# RescueLS.net
KiCad netlist of a schematic drawn in EAGLE
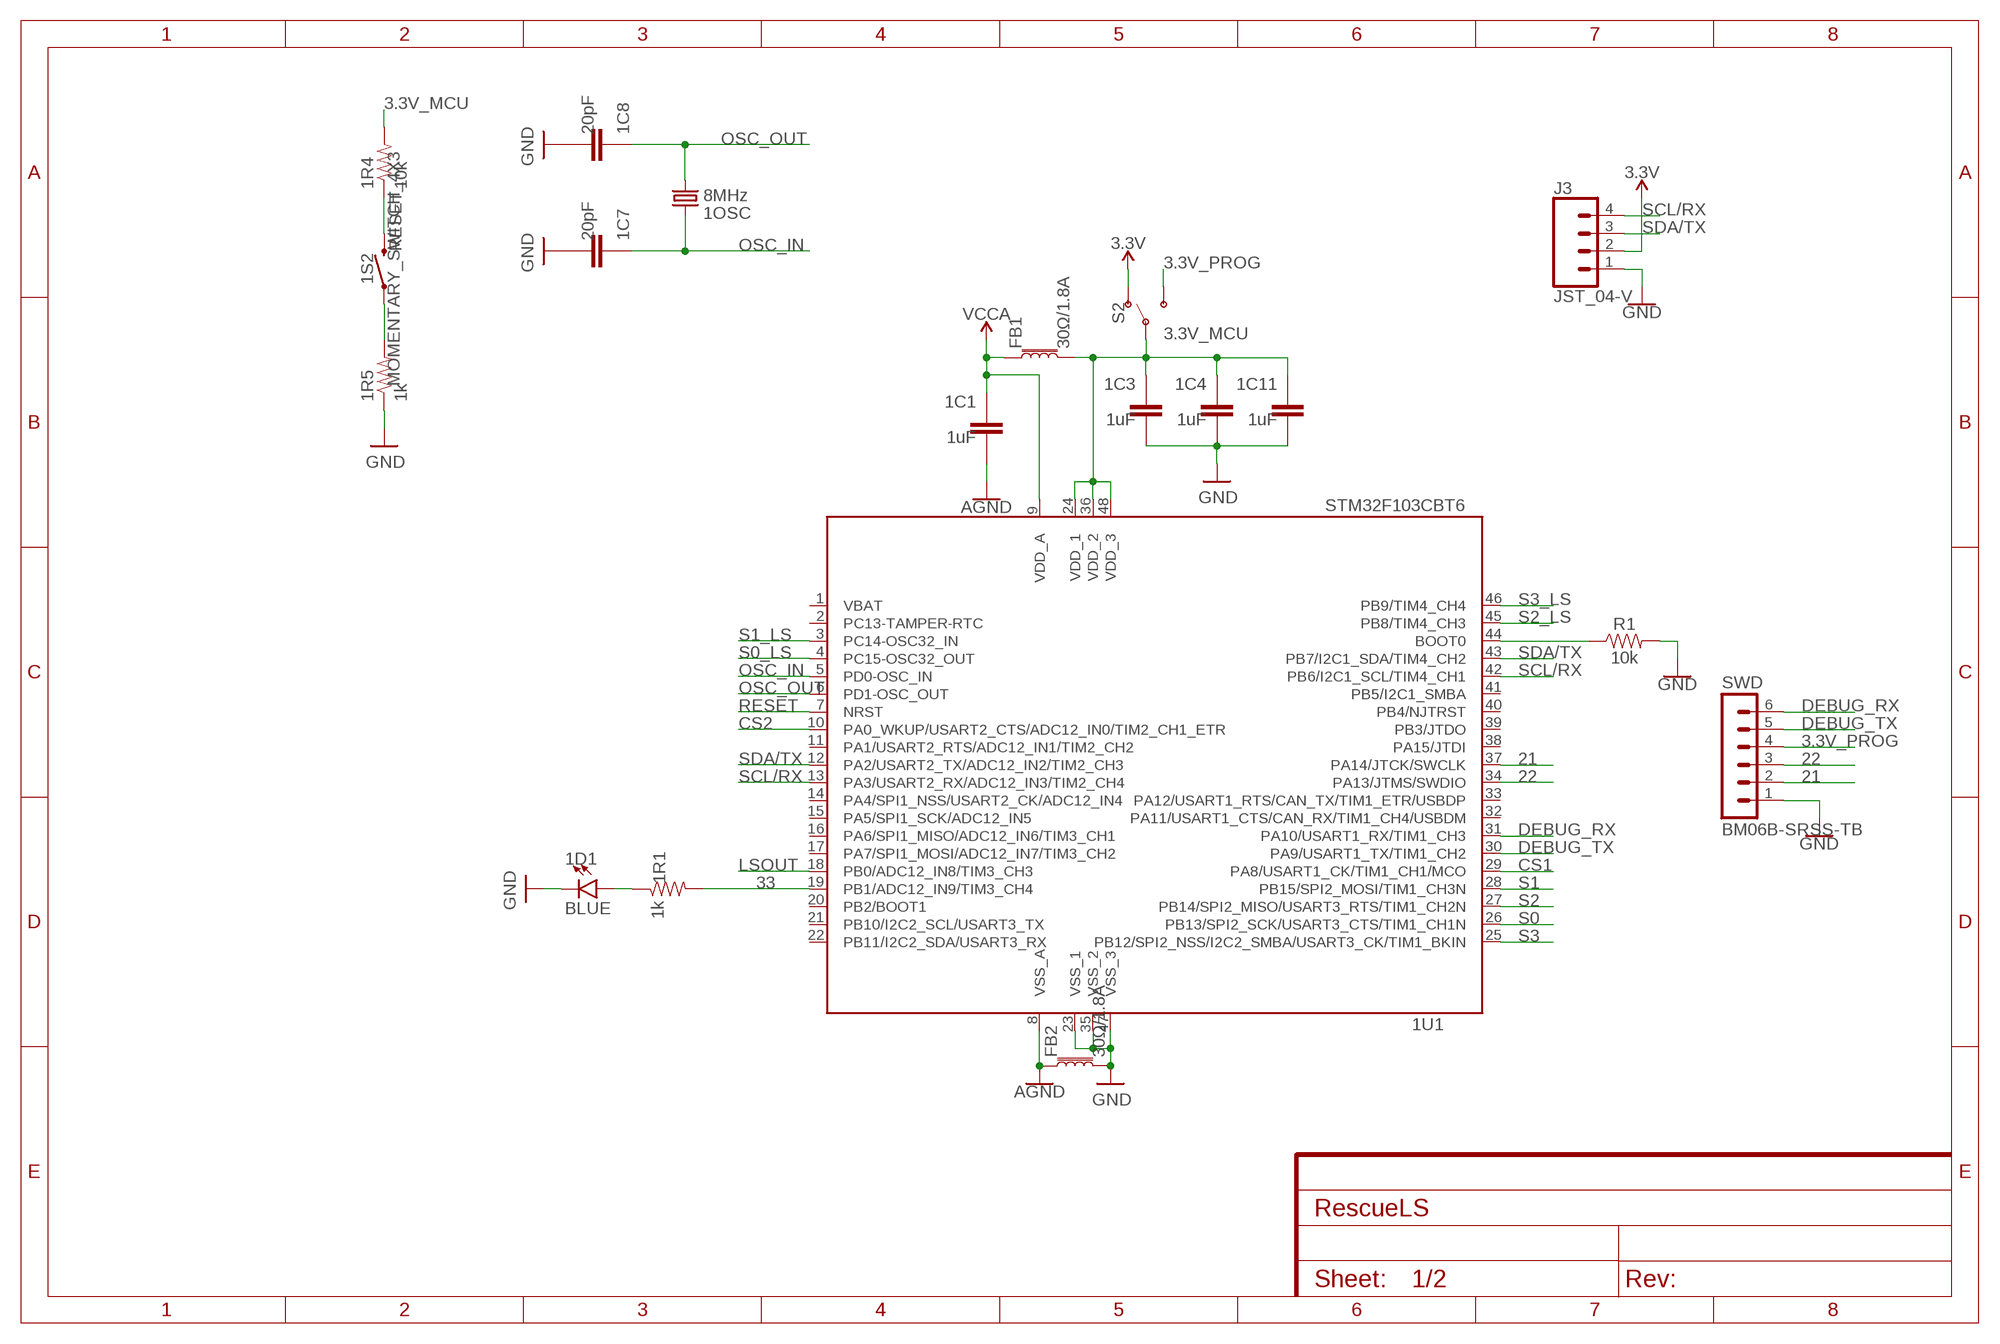
[diagram p0: schematic, sheet 1]
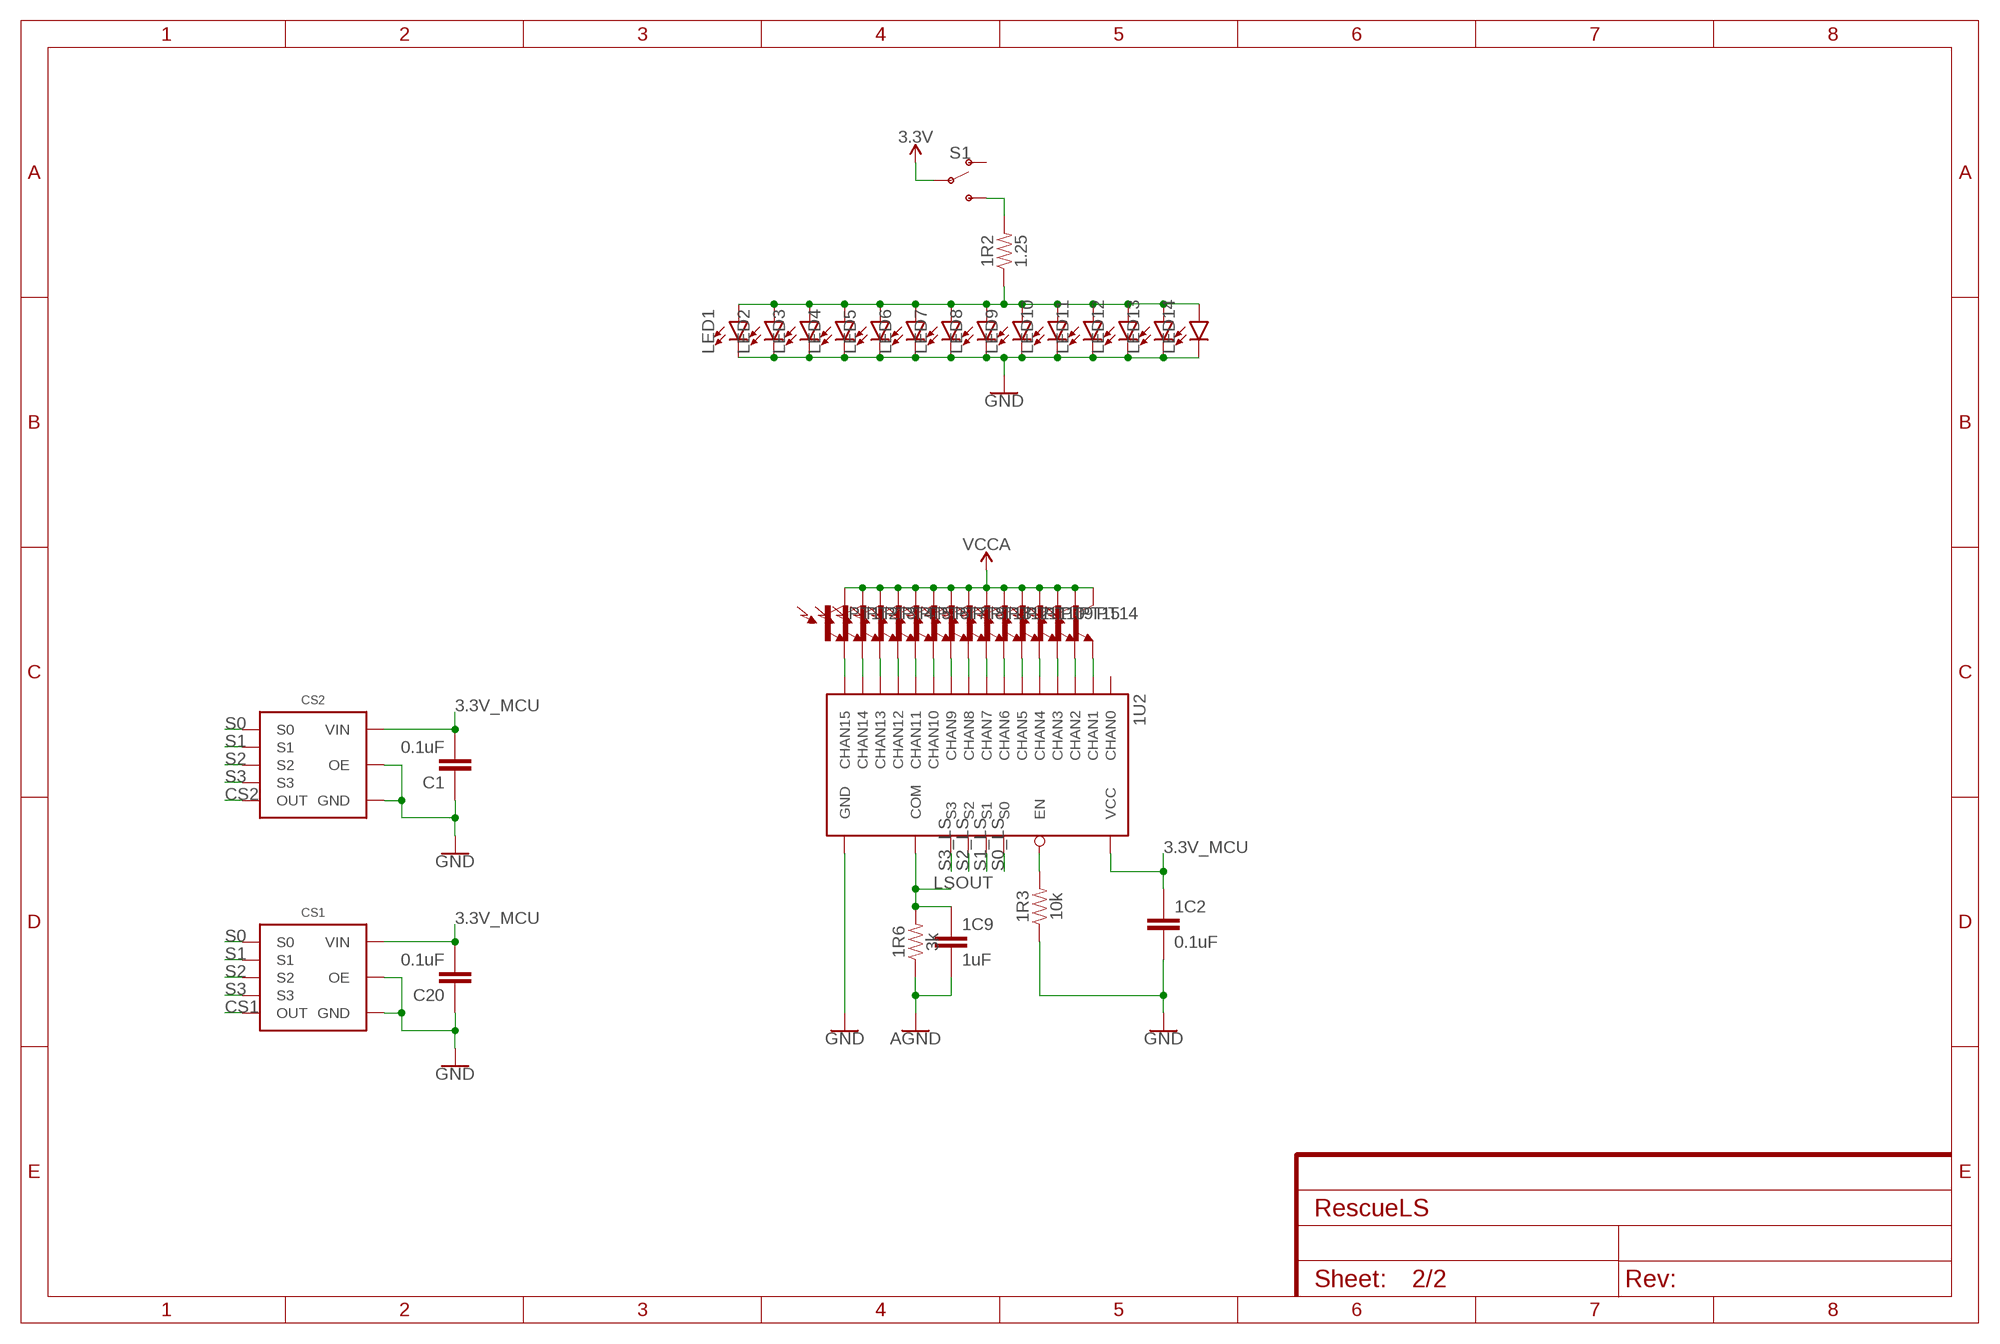
[diagram p1: schematic, sheet 2]

(export (version "E")
  (design (tool "Eeschema 10.0.6"))
  (components
    (comp (ref "1C1")
      (value "1uF")
      (footprint "eagle-import:C0603")
      (libsource (lib "eagle-import") (part "CAPACITOR0603"))
    )
    (comp (ref "1C3")
      (value "1uF")
      (footprint "eagle-import:C0603")
      (libsource (lib "eagle-import") (part "CAPACITOR0603"))
    )
    (comp (ref "1C4")
      (value "1uF")
      (footprint "eagle-import:C0603")
      (libsource (lib "eagle-import") (part "CAPACITOR0603"))
    )
    (comp (ref "1C7")
      (value "20pF")
      (footprint "eagle-import:C0603")
      (libsource (lib "eagle-import") (part "CAPACITOR0603"))
    )
    (comp (ref "1C8")
      (value "20pF")
      (footprint "eagle-import:C0603")
      (libsource (lib "eagle-import") (part "CAPACITOR0603"))
    )
    (comp (ref "1C11")
      (value "1uF")
      (footprint "eagle-import:C0603")
      (libsource (lib "eagle-import") (part "CAPACITOR0603"))
    )
    (comp (ref "1D1")
      (value "BLUE")
      (footprint "eagle-import:LED-0603")
      (libsource (lib "eagle-import") (part "LED-BLUE0603"))
    )
    (comp (ref "1OSC")
      (value "8MHz")
      (footprint "eagle-import:CRYSTAL-SMD-5X3.2-2PAD")
      (libsource (lib "eagle-import") (part "CRYSTALSMD-5X3.2-2PAD"))
    )
    (comp (ref "1R1")
      (value "1k")
      (footprint "eagle-import:R0603")
      (libsource (lib "eagle-import") (part "RESISTOR0603"))
    )
    (comp (ref "1R4")
      (value "10k")
      (footprint "eagle-import:R0603")
      (libsource (lib "eagle-import") (part "RESISTOR0603"))
    )
    (comp (ref "1R5")
      (value "1k")
      (footprint "eagle-import:R0603")
      (libsource (lib "eagle-import") (part "RESISTOR0603"))
    )
    (comp (ref "1S2")
      (value "MOMENTARY_SWITCH_4X3")
      (footprint "eagle-import:MOMENTARY_SWITCH_4X3")
      (libsource (lib "eagle-import") (part "MOMENTARY_SWITCH_4X3"))
    )
    (comp (ref "1U1")
      (value "STM32F103CBT6")
      (footprint "eagle-import:LQFP48")
      (libsource (lib "eagle-import") (part "STM32F103CBT6"))
    )
    (comp (ref "FB1")
      (value "30Ω/1.8A")
      (footprint "eagle-import:0603")
      (libsource (lib "eagle-import") (part "FERRITE_BEAD-0603"))
    )
    (comp (ref "FB2")
      (value "30Ω/1.8A")
      (footprint "eagle-import:0603")
      (libsource (lib "eagle-import") (part "FERRITE_BEAD-0603"))
    )
    (comp (ref "J3")
      (value "JST_04-V")
      (footprint "eagle-import:JST_04-V")
      (libsource (lib "eagle-import") (part "JST_04-V"))
    )
    (comp (ref "R1")
      (value "10k")
      (footprint "eagle-import:R0603")
      (libsource (lib "eagle-import") (part "RESISTOR0603"))
    )
    (comp (ref "S2")
      (value "SWITCH-SPDT-PTH-11.6X4.0MM-LOCK")
      (footprint "eagle-import:SWITCH_SPDT_PTH_11.6X4.0MM_LOCK")
      (libsource (lib "eagle-import") (part "SWITCH-SPDT-PTH-11.6X4.0MM-LOCK"))
    )
    (comp (ref "SWD")
      (value "BM06B-SRSS-TB")
      (footprint "eagle-import:BM06B-SRSS-TB")
      (libsource (lib "eagle-import") (part "BM06B-SRSS-TB"))
    )
    (comp (ref "1C2")
      (value "0.1uF")
      (footprint "eagle-import:C0603")
      (libsource (lib "eagle-import") (part "CAPACITOR0603"))
    )
    (comp (ref "1C9")
      (value "1uF")
      (footprint "eagle-import:C0603")
      (libsource (lib "eagle-import") (part "CAPACITOR0603"))
    )
    (comp (ref "1R2")
      (value "1.25")
      (footprint "eagle-import:R0603")
      (libsource (lib "eagle-import") (part "RESISTOR0603"))
    )
    (comp (ref "1R3")
      (value "10k")
      (footprint "eagle-import:R0603")
      (libsource (lib "eagle-import") (part "RESISTOR0603"))
    )
    (comp (ref "1R6")
      (value "3k")
      (footprint "eagle-import:R0603")
      (libsource (lib "eagle-import") (part "RESISTOR0603"))
    )
    (comp (ref "1U2")
      (value "74HC4067")
      (footprint "eagle-import:SOIC-24")
      (libsource (lib "eagle-import") (part "74HC4067"))
    )
    (comp (ref "C1")
      (value "0.1uF")
      (footprint "eagle-import:C0603")
      (libsource (lib "eagle-import") (part "CAPACITOR0603"))
    )
    (comp (ref "C20")
      (value "0.1uF")
      (footprint "eagle-import:C0603")
      (libsource (lib "eagle-import") (part "CAPACITOR0603"))
    )
    (comp (ref "CS1")
      (value "TCS3200")
      (footprint "eagle-import:SOIC-8")
      (libsource (lib "eagle-import") (part "TCS3200"))
    )
    (comp (ref "CS2")
      (value "TCS3200")
      (footprint "eagle-import:SOIC-8")
      (libsource (lib "eagle-import") (part "TCS3200"))
    )
    (comp (ref "LED1")
      (value "3528LED")
      (footprint "eagle-import:3528")
      (libsource (lib "eagle-import") (part "3528LED"))
    )
    (comp (ref "LED2")
      (value "3528LED")
      (footprint "eagle-import:3528")
      (libsource (lib "eagle-import") (part "3528LED"))
    )
    (comp (ref "LED3")
      (value "3528LED")
      (footprint "eagle-import:3528")
      (libsource (lib "eagle-import") (part "3528LED"))
    )
    (comp (ref "LED4")
      (value "3528LED")
      (footprint "eagle-import:3528")
      (libsource (lib "eagle-import") (part "3528LED"))
    )
    (comp (ref "LED5")
      (value "3528LED")
      (footprint "eagle-import:3528")
      (libsource (lib "eagle-import") (part "3528LED"))
    )
    (comp (ref "LED6")
      (value "3528LED")
      (footprint "eagle-import:3528")
      (libsource (lib "eagle-import") (part "3528LED"))
    )
    (comp (ref "LED7")
      (value "3528LED")
      (footprint "eagle-import:3528")
      (libsource (lib "eagle-import") (part "3528LED"))
    )
    (comp (ref "LED8")
      (value "3528LED")
      (footprint "eagle-import:3528")
      (libsource (lib "eagle-import") (part "3528LED"))
    )
    (comp (ref "LED9")
      (value "3528LED")
      (footprint "eagle-import:3528")
      (libsource (lib "eagle-import") (part "3528LED"))
    )
    (comp (ref "LED10")
      (value "3528LED")
      (footprint "eagle-import:3528")
      (libsource (lib "eagle-import") (part "3528LED"))
    )
    (comp (ref "LED11")
      (value "3528LED")
      (footprint "eagle-import:3528")
      (libsource (lib "eagle-import") (part "3528LED"))
    )
    (comp (ref "LED12")
      (value "3528LED")
      (footprint "eagle-import:3528")
      (libsource (lib "eagle-import") (part "3528LED"))
    )
    (comp (ref "LED13")
      (value "3528LED")
      (footprint "eagle-import:3528")
      (libsource (lib "eagle-import") (part "3528LED"))
    )
    (comp (ref "LED14")
      (value "3528LED")
      (footprint "eagle-import:3528")
      (libsource (lib "eagle-import") (part "3528LED"))
    )
    (comp (ref "PT1")
      (value "LIGHT_SENSORALS")
      (footprint "eagle-import:ALS-PT19")
      (libsource (lib "eagle-import") (part "LIGHT_SENSORALS"))
    )
    (comp (ref "PT2")
      (value "LIGHT_SENSORALS")
      (footprint "eagle-import:ALS-PT19")
      (libsource (lib "eagle-import") (part "LIGHT_SENSORALS"))
    )
    (comp (ref "PT3")
      (value "LIGHT_SENSORALS")
      (footprint "eagle-import:ALS-PT19")
      (libsource (lib "eagle-import") (part "LIGHT_SENSORALS"))
    )
    (comp (ref "PT4")
      (value "LIGHT_SENSORALS")
      (footprint "eagle-import:ALS-PT19")
      (libsource (lib "eagle-import") (part "LIGHT_SENSORALS"))
    )
    (comp (ref "PT5")
      (value "LIGHT_SENSORALS")
      (footprint "eagle-import:ALS-PT19")
      (libsource (lib "eagle-import") (part "LIGHT_SENSORALS"))
    )
    (comp (ref "PT6")
      (value "LIGHT_SENSORALS")
      (footprint "eagle-import:ALS-PT19")
      (libsource (lib "eagle-import") (part "LIGHT_SENSORALS"))
    )
    (comp (ref "PT7")
      (value "LIGHT_SENSORALS")
      (footprint "eagle-import:ALS-PT19")
      (libsource (lib "eagle-import") (part "LIGHT_SENSORALS"))
    )
    (comp (ref "PT8")
      (value "LIGHT_SENSORALS")
      (footprint "eagle-import:ALS-PT19")
      (libsource (lib "eagle-import") (part "LIGHT_SENSORALS"))
    )
    (comp (ref "PT9")
      (value "LIGHT_SENSORALS")
      (footprint "eagle-import:ALS-PT19")
      (libsource (lib "eagle-import") (part "LIGHT_SENSORALS"))
    )
    (comp (ref "PT10")
      (value "LIGHT_SENSORALS")
      (footprint "eagle-import:ALS-PT19")
      (libsource (lib "eagle-import") (part "LIGHT_SENSORALS"))
    )
    (comp (ref "PT11")
      (value "LIGHT_SENSORALS")
      (footprint "eagle-import:ALS-PT19")
      (libsource (lib "eagle-import") (part "LIGHT_SENSORALS"))
    )
    (comp (ref "PT12")
      (value "LIGHT_SENSORALS")
      (footprint "eagle-import:ALS-PT19")
      (libsource (lib "eagle-import") (part "LIGHT_SENSORALS"))
    )
    (comp (ref "PT13")
      (value "LIGHT_SENSORALS")
      (footprint "eagle-import:ALS-PT19")
      (libsource (lib "eagle-import") (part "LIGHT_SENSORALS"))
    )
    (comp (ref "PT14")
      (value "LIGHT_SENSORALS")
      (footprint "eagle-import:ALS-PT19")
      (libsource (lib "eagle-import") (part "LIGHT_SENSORALS"))
    )
    (comp (ref "PT15")
      (value "LIGHT_SENSORALS")
      (footprint "eagle-import:ALS-PT19")
      (libsource (lib "eagle-import") (part "LIGHT_SENSORALS"))
    )
    (comp (ref "S1")
      (value "SWITCH-SPDT-PTH-11.6X4.0MM-LOCK")
      (footprint "eagle-import:SWITCH_SPDT_PTH_11.6X4.0MM_LOCK")
      (libsource (lib "eagle-import") (part "SWITCH-SPDT-PTH-11.6X4.0MM-LOCK"))
    )
  )
  (nets
    (net (code "1") (name "3.3V") (class "Default")
      (node (ref "J3") (pin "2") (pinfunction "2_2") (pintype "passive"))
      (node (ref "S1") (pin "2") (pinfunction "P_2") (pintype "passive"))
      (node (ref "S2") (pin "1") (pinfunction "O_1") (pintype "passive"))
    )
    (net (code "2") (name "3.3V_MCU") (class "Default")
      (node (ref "1C11") (pin "1") (pinfunction "1_1") (pintype "passive"))
      (node (ref "1C2") (pin "1") (pinfunction "1_1") (pintype "passive"))
      (node (ref "1C3") (pin "1") (pinfunction "1_1") (pintype "passive"))
      (node (ref "1C4") (pin "1") (pinfunction "1_1") (pintype "passive"))
      (node (ref "1R4") (pin "2") (pinfunction "2_2") (pintype "passive"))
      (node (ref "1U1") (pin "24") (pinfunction "VDD_1_24") (pintype "power_in"))
      (node (ref "1U1") (pin "36") (pinfunction "VDD_2_36") (pintype "power_in"))
      (node (ref "1U1") (pin "48") (pinfunction "VDD_3_48") (pintype "power_in"))
      (node (ref "1U2") (pin "P24") (pinfunction "VCC_P24") (pintype "bidirectional"))
      (node (ref "C1") (pin "2") (pinfunction "2_2") (pintype "passive"))
      (node (ref "C20") (pin "2") (pinfunction "2_2") (pintype "passive"))
      (node (ref "CS1") (pin "5") (pinfunction "VIN_5") (pintype "bidirectional"))
      (node (ref "CS2") (pin "5") (pinfunction "VIN_5") (pintype "bidirectional"))
      (node (ref "FB1") (pin "2") (pinfunction "2_2") (pintype "passive"))
      (node (ref "S2") (pin "2") (pinfunction "P_2") (pintype "passive"))
    )
    (net (code "3") (name "3.3V_PROG") (class "Default")
      (node (ref "S2") (pin "3") (pinfunction "S_3") (pintype "passive"))
      (node (ref "SWD") (pin "4") (pinfunction "4_4") (pintype "passive"))
    )
    (net (code "4") (name "21") (class "Default")
      (node (ref "1U1") (pin "37") (pinfunction "PA14/JTCK/SWCLK_37") (pintype "bidirectional"))
      (node (ref "SWD") (pin "2") (pinfunction "2_2") (pintype "passive"))
    )
    (net (code "5") (name "22") (class "Default")
      (node (ref "1U1") (pin "34") (pinfunction "PA13/JTMS/SWDIO_34") (pintype "bidirectional"))
      (node (ref "SWD") (pin "3") (pinfunction "3_3") (pintype "passive"))
    )
    (net (code "6") (name "33") (class "Default")
      (node (ref "1R1") (pin "2") (pinfunction "2_2") (pintype "passive"))
      (node (ref "1U1") (pin "19") (pinfunction "PB1/ADC12_IN9/TIM3_CH4_19") (pintype "bidirectional"))
    )
    (net (code "7") (name "AGND") (class "Default")
      (node (ref "1C1") (pin "2") (pinfunction "2_2") (pintype "passive"))
      (node (ref "1C9") (pin "2") (pinfunction "2_2") (pintype "passive"))
      (node (ref "1R6") (pin "1") (pinfunction "1_1") (pintype "passive"))
      (node (ref "1U1") (pin "8") (pinfunction "VSS_A_8") (pintype "power_in"))
      (node (ref "FB2") (pin "1") (pinfunction "1_1") (pintype "passive"))
    )
    (net (code "8") (name "CS1") (class "Default")
      (node (ref "1U1") (pin "29") (pinfunction "PA8/USART1_CK/TIM1_CH1/MCO_29") (pintype "bidirectional"))
      (node (ref "CS1") (pin "6") (pinfunction "OUT_6") (pintype "bidirectional"))
    )
    (net (code "9") (name "CS2") (class "Default")
      (node (ref "1U1") (pin "10") (pinfunction "PA0_WKUP/USART2_CTS/ADC12_IN0/TIM2_CH1_ETR_10") (pintype "bidirectional"))
      (node (ref "CS2") (pin "6") (pinfunction "OUT_6") (pintype "bidirectional"))
    )
    (net (code "10") (name "DEBUG_RX") (class "Default")
      (node (ref "1U1") (pin "31") (pinfunction "PA10/USART1_RX/TIM1_CH3_31") (pintype "bidirectional"))
      (node (ref "SWD") (pin "6") (pinfunction "6_6") (pintype "passive"))
    )
    (net (code "11") (name "DEBUG_TX") (class "Default")
      (node (ref "1U1") (pin "30") (pinfunction "PA9/USART1_TX/TIM1_CH2_30") (pintype "input"))
      (node (ref "SWD") (pin "5") (pinfunction "5_5") (pintype "passive"))
    )
    (net (code "12") (name "GND") (class "Default")
      (node (ref "1C11") (pin "2") (pinfunction "2_2") (pintype "passive"))
      (node (ref "1C2") (pin "2") (pinfunction "2_2") (pintype "passive"))
      (node (ref "1C3") (pin "2") (pinfunction "2_2") (pintype "passive"))
      (node (ref "1C4") (pin "2") (pinfunction "2_2") (pintype "passive"))
      (node (ref "1C7") (pin "2") (pinfunction "2_2") (pintype "passive"))
      (node (ref "1C8") (pin "2") (pinfunction "2_2") (pintype "passive"))
      (node (ref "1D1") (pin "C") (pinfunction "C_C") (pintype "passive"))
      (node (ref "1R3") (pin "1") (pinfunction "1_1") (pintype "passive"))
      (node (ref "1R5") (pin "1") (pinfunction "1_1") (pintype "passive"))
      (node (ref "1U1") (pin "23") (pinfunction "VSS_1_23") (pintype "power_in"))
      (node (ref "1U1") (pin "35") (pinfunction "VSS_2_35") (pintype "power_in"))
      (node (ref "1U1") (pin "47") (pinfunction "VSS_3_47") (pintype "power_in"))
      (node (ref "1U2") (pin "P12") (pinfunction "GND_P12") (pintype "bidirectional"))
      (node (ref "C1") (pin "1") (pinfunction "1_1") (pintype "passive"))
      (node (ref "C20") (pin "1") (pinfunction "1_1") (pintype "passive"))
      (node (ref "CS1") (pin "3") (pinfunction "OE_3") (pintype "bidirectional"))
      (node (ref "CS1") (pin "4") (pinfunction "GND_4") (pintype "bidirectional"))
      (node (ref "CS2") (pin "3") (pinfunction "OE_3") (pintype "bidirectional"))
      (node (ref "CS2") (pin "4") (pinfunction "GND_4") (pintype "bidirectional"))
      (node (ref "FB2") (pin "2") (pinfunction "2_2") (pintype "passive"))
      (node (ref "J3") (pin "1") (pinfunction "1_1") (pintype "passive"))
      (node (ref "LED1") (pin "C") (pinfunction "C_C") (pintype "passive"))
      (node (ref "LED10") (pin "C") (pinfunction "C_C") (pintype "passive"))
      (node (ref "LED11") (pin "C") (pinfunction "C_C") (pintype "passive"))
      (node (ref "LED12") (pin "C") (pinfunction "C_C") (pintype "passive"))
      (node (ref "LED13") (pin "C") (pinfunction "C_C") (pintype "passive"))
      (node (ref "LED14") (pin "C") (pinfunction "C_C") (pintype "passive"))
      (node (ref "LED2") (pin "C") (pinfunction "C_C") (pintype "passive"))
      (node (ref "LED3") (pin "C") (pinfunction "C_C") (pintype "passive"))
      (node (ref "LED4") (pin "C") (pinfunction "C_C") (pintype "passive"))
      (node (ref "LED5") (pin "C") (pinfunction "C_C") (pintype "passive"))
      (node (ref "LED6") (pin "C") (pinfunction "C_C") (pintype "passive"))
      (node (ref "LED7") (pin "C") (pinfunction "C_C") (pintype "passive"))
      (node (ref "LED8") (pin "C") (pinfunction "C_C") (pintype "passive"))
      (node (ref "LED9") (pin "C") (pinfunction "C_C") (pintype "passive"))
      (node (ref "R1") (pin "2") (pinfunction "2_2") (pintype "passive"))
      (node (ref "SWD") (pin "1") (pinfunction "1_1") (pintype "passive"))
    )
    (net (code "13") (name "LSOUT") (class "Default")
      (node (ref "1C9") (pin "1") (pinfunction "1_1") (pintype "passive"))
      (node (ref "1R6") (pin "2") (pinfunction "2_2") (pintype "passive"))
      (node (ref "1U1") (pin "18") (pinfunction "PB0/ADC12_IN8/TIM3_CH3_18") (pintype "bidirectional"))
      (node (ref "1U2") (pin "P1") (pinfunction "COM_P1") (pintype "bidirectional"))
    )
    (net (code "14") (name "Net-(1D1-PadA)") (class "Default")
      (node (ref "1D1") (pin "A") (pinfunction "A_A") (pintype "passive"))
      (node (ref "1R1") (pin "1") (pinfunction "1_1") (pintype "passive"))
    )
    (net (code "15") (name "Net-(1R2-Pad1)") (class "Default")
      (node (ref "1R2") (pin "1") (pinfunction "1_1") (pintype "passive"))
      (node (ref "LED1") (pin "A") (pinfunction "A_A") (pintype "passive"))
      (node (ref "LED10") (pin "A") (pinfunction "A_A") (pintype "passive"))
      (node (ref "LED11") (pin "A") (pinfunction "A_A") (pintype "passive"))
      (node (ref "LED12") (pin "A") (pinfunction "A_A") (pintype "passive"))
      (node (ref "LED13") (pin "A") (pinfunction "A_A") (pintype "passive"))
      (node (ref "LED14") (pin "A") (pinfunction "A_A") (pintype "passive"))
      (node (ref "LED2") (pin "A") (pinfunction "A_A") (pintype "passive"))
      (node (ref "LED3") (pin "A") (pinfunction "A_A") (pintype "passive"))
      (node (ref "LED4") (pin "A") (pinfunction "A_A") (pintype "passive"))
      (node (ref "LED5") (pin "A") (pinfunction "A_A") (pintype "passive"))
      (node (ref "LED6") (pin "A") (pinfunction "A_A") (pintype "passive"))
      (node (ref "LED7") (pin "A") (pinfunction "A_A") (pintype "passive"))
      (node (ref "LED8") (pin "A") (pinfunction "A_A") (pintype "passive"))
      (node (ref "LED9") (pin "A") (pinfunction "A_A") (pintype "passive"))
    )
    (net (code "16") (name "Net-(1S2-1)") (class "Default")
      (node (ref "1R5") (pin "2") (pinfunction "2_2") (pintype "passive"))
      (node (ref "1S2") (pin "P$1") (pinfunction "1_P$1") (pintype "passive"))
    )
    (net (code "17") (name "Net-(1U1-BOOT0)") (class "Default")
      (node (ref "1U1") (pin "44") (pinfunction "BOOT0_44") (pintype "input"))
      (node (ref "R1") (pin "1") (pinfunction "1_1") (pintype "passive"))
    )
    (net (code "18") (name "Net-(1U2-CHAN1)") (class "Default")
      (node (ref "1U2") (pin "P8") (pinfunction "CHAN1_P8") (pintype "bidirectional"))
      (node (ref "PT14") (pin "E") (pinfunction "E1_E") (pintype "passive"))
    )
    (net (code "19") (name "Net-(1U2-CHAN2)") (class "Default")
      (node (ref "1U2") (pin "P7") (pinfunction "CHAN2_P7") (pintype "bidirectional"))
      (node (ref "PT15") (pin "E") (pinfunction "E1_E") (pintype "passive"))
    )
    (net (code "20") (name "Net-(1U2-CHAN3)") (class "Default")
      (node (ref "1U2") (pin "P6") (pinfunction "CHAN3_P6") (pintype "bidirectional"))
      (node (ref "PT9") (pin "E") (pinfunction "E1_E") (pintype "passive"))
    )
    (net (code "21") (name "Net-(1U2-CHAN4)") (class "Default")
      (node (ref "1U2") (pin "P5") (pinfunction "CHAN4_P5") (pintype "bidirectional"))
      (node (ref "PT10") (pin "E") (pinfunction "E1_E") (pintype "passive"))
    )
    (net (code "22") (name "Net-(1U2-CHAN5)") (class "Default")
      (node (ref "1U2") (pin "P4") (pinfunction "CHAN5_P4") (pintype "bidirectional"))
      (node (ref "PT11") (pin "E") (pinfunction "E1_E") (pintype "passive"))
    )
    (net (code "23") (name "Net-(1U2-CHAN6)") (class "Default")
      (node (ref "1U2") (pin "P3") (pinfunction "CHAN6_P3") (pintype "bidirectional"))
      (node (ref "PT12") (pin "E") (pinfunction "E1_E") (pintype "passive"))
    )
    (net (code "24") (name "Net-(1U2-CHAN7)") (class "Default")
      (node (ref "1U2") (pin "P2") (pinfunction "CHAN7_P2") (pintype "bidirectional"))
      (node (ref "PT13") (pin "E") (pinfunction "E1_E") (pintype "passive"))
    )
    (net (code "25") (name "Net-(1U2-CHAN8)") (class "Default")
      (node (ref "1U2") (pin "P23") (pinfunction "CHAN8_P23") (pintype "bidirectional"))
      (node (ref "PT8") (pin "E") (pinfunction "E1_E") (pintype "passive"))
    )
    (net (code "26") (name "Net-(1U2-CHAN9)") (class "Default")
      (node (ref "1U2") (pin "P22") (pinfunction "CHAN9_P22") (pintype "bidirectional"))
      (node (ref "PT7") (pin "E") (pinfunction "E1_E") (pintype "passive"))
    )
    (net (code "27") (name "Net-(1U2-CHAN10)") (class "Default")
      (node (ref "1U2") (pin "P21") (pinfunction "CHAN10_P21") (pintype "bidirectional"))
      (node (ref "PT6") (pin "E") (pinfunction "E1_E") (pintype "passive"))
    )
    (net (code "28") (name "Net-(1U2-CHAN11)") (class "Default")
      (node (ref "1U2") (pin "P20") (pinfunction "CHAN11_P20") (pintype "bidirectional"))
      (node (ref "PT5") (pin "E") (pinfunction "E1_E") (pintype "passive"))
    )
    (net (code "29") (name "Net-(1U2-CHAN12)") (class "Default")
      (node (ref "1U2") (pin "P19") (pinfunction "CHAN12_P19") (pintype "bidirectional"))
      (node (ref "PT4") (pin "E") (pinfunction "E1_E") (pintype "passive"))
    )
    (net (code "30") (name "Net-(1U2-CHAN13)") (class "Default")
      (node (ref "1U2") (pin "P18") (pinfunction "CHAN13_P18") (pintype "bidirectional"))
      (node (ref "PT3") (pin "E") (pinfunction "E1_E") (pintype "passive"))
    )
    (net (code "31") (name "Net-(1U2-CHAN14)") (class "Default")
      (node (ref "1U2") (pin "P17") (pinfunction "CHAN14_P17") (pintype "bidirectional"))
      (node (ref "PT2") (pin "E") (pinfunction "E1_E") (pintype "passive"))
    )
    (net (code "32") (name "Net-(1U2-CHAN15)") (class "Default")
      (node (ref "1U2") (pin "P16") (pinfunction "CHAN15_P16") (pintype "bidirectional"))
      (node (ref "PT1") (pin "E") (pinfunction "E1_E") (pintype "passive"))
    )
    (net (code "33") (name "Net-(1U2-EN)") (class "Default")
      (node (ref "1R3") (pin "2") (pinfunction "2_2") (pintype "passive"))
      (node (ref "1U2") (pin "P15") (pinfunction "EN_P15") (pintype "input"))
    )
    (net (code "34") (name "Net-(S1-S)") (class "Default")
      (node (ref "1R2") (pin "2") (pinfunction "2_2") (pintype "passive"))
      (node (ref "S1") (pin "3") (pinfunction "S_3") (pintype "passive"))
    )
    (net (code "35") (name "OSC_IN") (class "Default")
      (node (ref "1C7") (pin "1") (pinfunction "1_1") (pintype "passive"))
      (node (ref "1OSC") (pin "P$2") (pinfunction "2_P$2") (pintype "passive"))
      (node (ref "1U1") (pin "5") (pinfunction "PD0-OSC_IN_5") (pintype "input"))
    )
    (net (code "36") (name "OSC_OUT") (class "Default")
      (node (ref "1C8") (pin "1") (pinfunction "1_1") (pintype "passive"))
      (node (ref "1OSC") (pin "P$1") (pinfunction "1_P$1") (pintype "passive"))
      (node (ref "1U1") (pin "6") (pinfunction "PD1-OSC_OUT_6") (pintype "input"))
    )
    (net (code "37") (name "RESET") (class "Default")
      (node (ref "1R4") (pin "1") (pinfunction "1_1") (pintype "passive"))
      (node (ref "1S2") (pin "P$2") (pinfunction "2_P$2") (pintype "passive"))
      (node (ref "1U1") (pin "7") (pinfunction "NRST_7") (pintype "input"))
    )
    (net (code "38") (name "S0") (class "Default")
      (node (ref "1U1") (pin "26") (pinfunction "PB13/SPI2_SCK/USART3_CTS/TIM1_CH1N_26") (pintype "input"))
      (node (ref "CS1") (pin "1") (pinfunction "S0_1") (pintype "bidirectional"))
      (node (ref "CS2") (pin "1") (pinfunction "S0_1") (pintype "bidirectional"))
    )
    (net (code "39") (name "S0_LS") (class "Default")
      (node (ref "1U1") (pin "4") (pinfunction "PC15-OSC32_OUT_4") (pintype "input"))
      (node (ref "1U2") (pin "P10") (pinfunction "S0_P10") (pintype "input"))
    )
    (net (code "40") (name "S1") (class "Default")
      (node (ref "1U1") (pin "28") (pinfunction "PB15/SPI2_MOSI/TIM1_CH3N_28") (pintype "input"))
      (node (ref "CS1") (pin "2") (pinfunction "S1_2") (pintype "bidirectional"))
      (node (ref "CS2") (pin "2") (pinfunction "S1_2") (pintype "bidirectional"))
    )
    (net (code "41") (name "S1_LS") (class "Default")
      (node (ref "1U1") (pin "3") (pinfunction "PC14-OSC32_IN_3") (pintype "input"))
      (node (ref "1U2") (pin "P11") (pinfunction "S1_P11") (pintype "input"))
    )
    (net (code "42") (name "S2") (class "Default")
      (node (ref "1U1") (pin "27") (pinfunction "PB14/SPI2_MISO/USART3_RTS/TIM1_CH2N_27") (pintype "input"))
      (node (ref "CS1") (pin "7") (pinfunction "S2_7") (pintype "bidirectional"))
      (node (ref "CS2") (pin "7") (pinfunction "S2_7") (pintype "bidirectional"))
    )
    (net (code "43") (name "S2_LS") (class "Default")
      (node (ref "1U1") (pin "45") (pinfunction "PB8/TIM4_CH3_45") (pintype "bidirectional"))
      (node (ref "1U2") (pin "P14") (pinfunction "S2_P14") (pintype "input"))
    )
    (net (code "44") (name "S3") (class "Default")
      (node (ref "1U1") (pin "25") (pinfunction "PB12/SPI2_NSS/I2C2_SMBA/USART3_CK/TIM1_BKIN_25") (pintype "input"))
      (node (ref "CS1") (pin "8") (pinfunction "S3_8") (pintype "bidirectional"))
      (node (ref "CS2") (pin "8") (pinfunction "S3_8") (pintype "bidirectional"))
    )
    (net (code "45") (name "S3_LS") (class "Default")
      (node (ref "1U1") (pin "46") (pinfunction "PB9/TIM4_CH4_46") (pintype "input"))
      (node (ref "1U2") (pin "P13") (pinfunction "S3_P13") (pintype "input"))
    )
    (net (code "46") (name "SCL{slash}RX") (class "Default")
      (node (ref "1U1") (pin "13") (pinfunction "PA3/USART2_RX/ADC12_IN3/TIM2_CH4_13") (pintype "bidirectional"))
      (node (ref "1U1") (pin "42") (pinfunction "PB6/I2C1_SCL/TIM4_CH1_42") (pintype "input"))
      (node (ref "J3") (pin "4") (pinfunction "4_4") (pintype "passive"))
    )
    (net (code "47") (name "SDA{slash}TX") (class "Default")
      (node (ref "1U1") (pin "12") (pinfunction "PA2/USART2_TX/ADC12_IN2/TIM2_CH3_12") (pintype "bidirectional"))
      (node (ref "1U1") (pin "43") (pinfunction "PB7/I2C1_SDA/TIM4_CH2_43") (pintype "bidirectional"))
      (node (ref "J3") (pin "3") (pinfunction "3_3") (pintype "passive"))
    )
    (net (code "48") (name "VBAT") (class "Default")
      (node (ref "1U1") (pin "1") (pinfunction "VBAT_1") (pintype "power_in"))
    )
    (net (code "49") (name "VCCA") (class "Default")
      (node (ref "1C1") (pin "1") (pinfunction "1_1") (pintype "passive"))
      (node (ref "1U1") (pin "9") (pinfunction "VDD_A_9") (pintype "power_in"))
      (node (ref "FB1") (pin "1") (pinfunction "1_1") (pintype "passive"))
      (node (ref "PT1") (pin "C") (pinfunction "C1_C") (pintype "passive"))
      (node (ref "PT10") (pin "C") (pinfunction "C1_C") (pintype "passive"))
      (node (ref "PT11") (pin "C") (pinfunction "C1_C") (pintype "passive"))
      (node (ref "PT12") (pin "C") (pinfunction "C1_C") (pintype "passive"))
      (node (ref "PT13") (pin "C") (pinfunction "C1_C") (pintype "passive"))
      (node (ref "PT14") (pin "C") (pinfunction "C1_C") (pintype "passive"))
      (node (ref "PT15") (pin "C") (pinfunction "C1_C") (pintype "passive"))
      (node (ref "PT2") (pin "C") (pinfunction "C1_C") (pintype "passive"))
      (node (ref "PT3") (pin "C") (pinfunction "C1_C") (pintype "passive"))
      (node (ref "PT4") (pin "C") (pinfunction "C1_C") (pintype "passive"))
      (node (ref "PT5") (pin "C") (pinfunction "C1_C") (pintype "passive"))
      (node (ref "PT6") (pin "C") (pinfunction "C1_C") (pintype "passive"))
      (node (ref "PT7") (pin "C") (pinfunction "C1_C") (pintype "passive"))
      (node (ref "PT8") (pin "C") (pinfunction "C1_C") (pintype "passive"))
      (node (ref "PT9") (pin "C") (pinfunction "C1_C") (pintype "passive"))
    )
    (net (code "50") (name "unconnected-(1U1-PA1{slash}USART2_RTS{slash}ADC12_IN1{slash}TIM2_CH2-Pad11)") (class "Default")
      (node (ref "1U1") (pin "11") (pinfunction "PA1/USART2_RTS/ADC12_IN1/TIM2_CH2_11") (pintype "bidirectional"))
    )
    (net (code "51") (name "unconnected-(1U1-PA4{slash}SPI1_NSS{slash}USART2_CK{slash}ADC12_IN4-Pad14)") (class "Default")
      (node (ref "1U1") (pin "14") (pinfunction "PA4/SPI1_NSS/USART2_CK/ADC12_IN4_14") (pintype "bidirectional"))
    )
    (net (code "52") (name "unconnected-(1U1-PA5{slash}SPI1_SCK{slash}ADC12_IN5-Pad15)") (class "Default")
      (node (ref "1U1") (pin "15") (pinfunction "PA5/SPI1_SCK/ADC12_IN5_15") (pintype "bidirectional"))
    )
    (net (code "53") (name "unconnected-(1U1-PA6{slash}SPI1_MISO{slash}ADC12_IN6{slash}TIM3_CH1-Pad16)") (class "Default")
      (node (ref "1U1") (pin "16") (pinfunction "PA6/SPI1_MISO/ADC12_IN6/TIM3_CH1_16") (pintype "bidirectional"))
    )
    (net (code "54") (name "unconnected-(1U1-PA7{slash}SPI1_MOSI{slash}ADC12_IN7{slash}TIM3_CH2-Pad17)") (class "Default")
      (node (ref "1U1") (pin "17") (pinfunction "PA7/SPI1_MOSI/ADC12_IN7/TIM3_CH2_17") (pintype "bidirectional"))
    )
    (net (code "55") (name "unconnected-(1U1-PA11{slash}USART1_CTS{slash}CAN_RX{slash}TIM1_CH4{slash}USBDM-Pad32)") (class "Default")
      (node (ref "1U1") (pin "32") (pinfunction "PA11/USART1_CTS/CAN_RX/TIM1_CH4/USBDM_32") (pintype "bidirectional"))
    )
    (net (code "56") (name "unconnected-(1U1-PA12{slash}USART1_RTS{slash}CAN_TX{slash}TIM1_ETR{slash}USBDP-Pad33)") (class "Default")
      (node (ref "1U1") (pin "33") (pinfunction "PA12/USART1_RTS/CAN_TX/TIM1_ETR/USBDP_33") (pintype "bidirectional"))
    )
    (net (code "57") (name "unconnected-(1U1-PA15{slash}JTDI-Pad38)") (class "Default")
      (node (ref "1U1") (pin "38") (pinfunction "PA15/JTDI_38") (pintype "bidirectional"))
    )
    (net (code "58") (name "unconnected-(1U1-PB2{slash}BOOT1-Pad20)") (class "Default")
      (node (ref "1U1") (pin "20") (pinfunction "PB2/BOOT1_20") (pintype "bidirectional"))
    )
    (net (code "59") (name "unconnected-(1U1-PB3{slash}JTDO-Pad39)") (class "Default")
      (node (ref "1U1") (pin "39") (pinfunction "PB3/JTDO_39") (pintype "bidirectional"))
    )
    (net (code "60") (name "unconnected-(1U1-PB4{slash}NJTRST-Pad40)") (class "Default")
      (node (ref "1U1") (pin "40") (pinfunction "PB4/NJTRST_40") (pintype "bidirectional"))
    )
    (net (code "61") (name "unconnected-(1U1-PB5{slash}I2C1_SMBA-Pad41)") (class "Default")
      (node (ref "1U1") (pin "41") (pinfunction "PB5/I2C1_SMBA_41") (pintype "input"))
    )
    (net (code "62") (name "unconnected-(1U1-PB10{slash}I2C2_SCL{slash}USART3_TX-Pad21)") (class "Default")
      (node (ref "1U1") (pin "21") (pinfunction "PB10/I2C2_SCL/USART3_TX_21") (pintype "input"))
    )
    (net (code "63") (name "unconnected-(1U1-PB11{slash}I2C2_SDA{slash}USART3_RX-Pad22)") (class "Default")
      (node (ref "1U1") (pin "22") (pinfunction "PB11/I2C2_SDA/USART3_RX_22") (pintype "input"))
    )
    (net (code "64") (name "unconnected-(1U1-PC13-TAMPER-RTC-Pad2)") (class "Default")
      (node (ref "1U1") (pin "2") (pinfunction "PC13-TAMPER-RTC_2") (pintype "input"))
    )
    (net (code "65") (name "unconnected-(1U2-CHAN0-PadP9)") (class "Default")
      (node (ref "1U2") (pin "P9") (pinfunction "CHAN0_P9") (pintype "bidirectional"))
    )
    (net (code "66") (name "unconnected-(S1-O-Pad1)") (class "Default")
      (node (ref "S1") (pin "1") (pinfunction "O_1") (pintype "passive"))
    )
  )
)
